# HEATER.net
KiCad netlist of a schematic drawn in Altium Designer
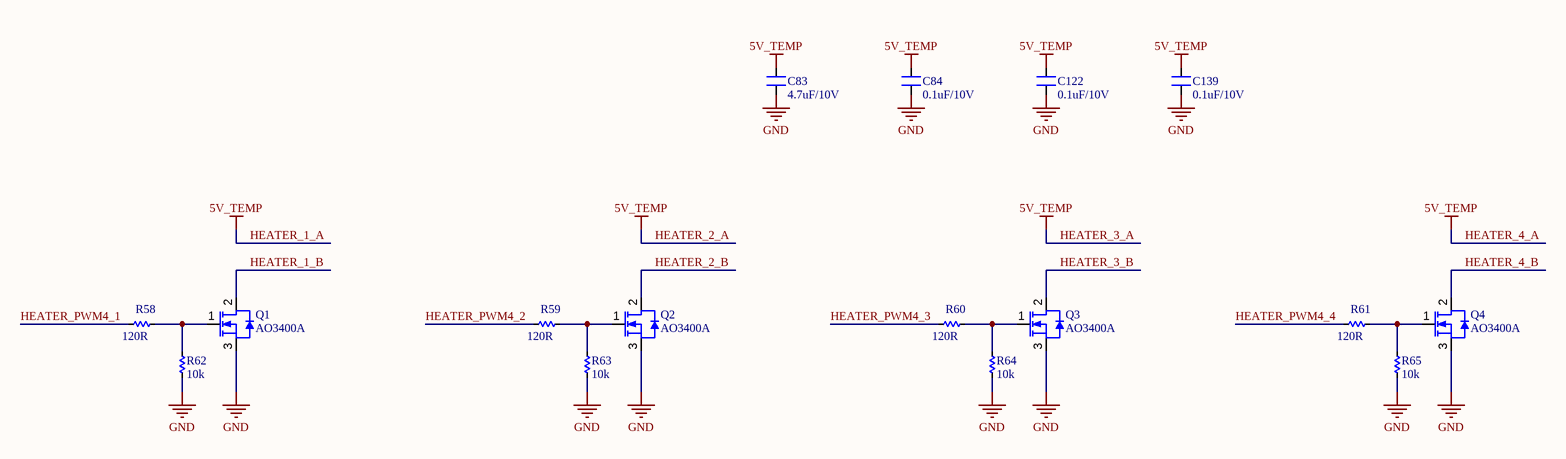
[diagram p0: HEATER.SchDoc]

(export (version "E")
  (design (tool "Eeschema 10.0.6"))
  (components
    (comp (ref "C83")
      (value "4.7uF/10V")
      (footprint "CAP_C_1608X80")
      (libsource (lib "EXP_HW_V3") (part "Capacitors"))
    )
    (comp (ref "C84")
      (value "0.1uF/10V")
      (footprint "CAP_C_1608X80")
      (libsource (lib "EXP_HW_V3") (part "Capacitors"))
    )
    (comp (ref "C122")
      (value "0.1uF/10V")
      (footprint "CAP_C_1608X80")
      (libsource (lib "EXP_HW_V3") (part "Capacitors"))
    )
    (comp (ref "C139")
      (value "0.1uF/10V")
      (footprint "CAP_C_1608X80")
      (libsource (lib "EXP_HW_V3") (part "Capacitors"))
    )
    (comp (ref "Q1")
      (value "AO3400A")
      (footprint "SOT23-13_2")
      (description "MOSFET N-CH 30V 5.7A SOT23-3L")
      (libsource (lib "EXP_HW_V3") (part "AO3400A"))
    )
    (comp (ref "Q2")
      (value "AO3400A")
      (footprint "SOT23-13_2")
      (description "MOSFET N-CH 30V 5.7A SOT23-3L")
      (libsource (lib "EXP_HW_V3") (part "AO3400A"))
    )
    (comp (ref "Q3")
      (value "AO3400A")
      (footprint "SOT23-13_2")
      (description "MOSFET N-CH 30V 5.7A SOT23-3L")
      (libsource (lib "EXP_HW_V3") (part "AO3400A"))
    )
    (comp (ref "Q4")
      (value "AO3400A")
      (footprint "SOT23-13_2")
      (description "MOSFET N-CH 30V 5.7A SOT23-3L")
      (libsource (lib "EXP_HW_V3") (part "AO3400A"))
    )
    (comp (ref "R58")
      (value "120R")
      (footprint "RES_C_1608X60")
      (description "SMD")
      (fields
        (field (name "MANUFACTURER") "Generic Components")
        (field (name "PUBLISHER") "Altium Hobart Technology Centre")
      )
      (libsource (lib "EXP_HW_V3") (part "Res SMD"))
    )
    (comp (ref "R59")
      (value "120R")
      (footprint "RES_C_1608X60")
      (description "SMD")
      (fields
        (field (name "MANUFACTURER") "Generic Components")
        (field (name "PUBLISHER") "Altium Hobart Technology Centre")
      )
      (libsource (lib "EXP_HW_V3") (part "Res SMD"))
    )
    (comp (ref "R60")
      (value "120R")
      (footprint "RES_C_1608X60")
      (description "SMD")
      (fields
        (field (name "MANUFACTURER") "Generic Components")
        (field (name "PUBLISHER") "Altium Hobart Technology Centre")
      )
      (libsource (lib "EXP_HW_V3") (part "Res SMD"))
    )
    (comp (ref "R61")
      (value "120R")
      (footprint "RES_C_1608X60")
      (description "SMD")
      (fields
        (field (name "MANUFACTURER") "Generic Components")
        (field (name "PUBLISHER") "Altium Hobart Technology Centre")
      )
      (libsource (lib "EXP_HW_V3") (part "Res SMD"))
    )
    (comp (ref "R62")
      (value "10k")
      (footprint "RES_C_1608X60")
      (description "SMD")
      (fields
        (field (name "MANUFACTURER") "Generic Components")
        (field (name "PUBLISHER") "Altium Hobart Technology Centre")
      )
      (libsource (lib "EXP_HW_V3") (part "Res SMD"))
    )
    (comp (ref "R63")
      (value "10k")
      (footprint "RES_C_1608X60")
      (description "SMD")
      (fields
        (field (name "MANUFACTURER") "Generic Components")
        (field (name "PUBLISHER") "Altium Hobart Technology Centre")
      )
      (libsource (lib "EXP_HW_V3") (part "Res SMD"))
    )
    (comp (ref "R64")
      (value "10k")
      (footprint "RES_C_1608X60")
      (description "SMD")
      (fields
        (field (name "MANUFACTURER") "Generic Components")
        (field (name "PUBLISHER") "Altium Hobart Technology Centre")
      )
      (libsource (lib "EXP_HW_V3") (part "Res SMD"))
    )
    (comp (ref "R65")
      (value "10k")
      (footprint "RES_C_1608X60")
      (description "SMD")
      (fields
        (field (name "MANUFACTURER") "Generic Components")
        (field (name "PUBLISHER") "Altium Hobart Technology Centre")
      )
      (libsource (lib "EXP_HW_V3") (part "Res SMD"))
    )
  )
  (nets
    (net (code "1") (name "/HEATER_1_B") (class "Default")
      (node (ref "Q1") (pin "2") (pinfunction "D_2") (pintype "passive"))
    )
    (net (code "2") (name "/HEATER_2_B") (class "Default")
      (node (ref "Q2") (pin "2") (pinfunction "D_2") (pintype "passive"))
    )
    (net (code "3") (name "/HEATER_3_B") (class "Default")
      (node (ref "Q3") (pin "2") (pinfunction "D_2") (pintype "passive"))
    )
    (net (code "4") (name "/HEATER_4_B") (class "Default")
      (node (ref "Q4") (pin "2") (pinfunction "D_2") (pintype "passive"))
    )
    (net (code "5") (name "/HEATER_PWM4_1") (class "Default")
      (node (ref "R58") (pin "1") (pinfunction "1_1") (pintype "passive"))
    )
    (net (code "6") (name "/HEATER_PWM4_2") (class "Default")
      (node (ref "R59") (pin "1") (pinfunction "1_1") (pintype "passive"))
    )
    (net (code "7") (name "/HEATER_PWM4_3") (class "Default")
      (node (ref "R60") (pin "1") (pinfunction "1_1") (pintype "passive"))
    )
    (net (code "8") (name "/HEATER_PWM4_4") (class "Default")
      (node (ref "R61") (pin "1") (pinfunction "1_1") (pintype "passive"))
    )
    (net (code "9") (name "5V_TEMP") (class "Default")
      (node (ref "C122") (pin "2") (pinfunction "2_2") (pintype "passive"))
      (node (ref "C139") (pin "2") (pinfunction "2_2") (pintype "passive"))
      (node (ref "C83") (pin "2") (pinfunction "2_2") (pintype "passive"))
      (node (ref "C84") (pin "2") (pinfunction "2_2") (pintype "passive"))
    )
    (net (code "10") (name "GND") (class "Default")
      (node (ref "C122") (pin "1") (pinfunction "1_1") (pintype "passive"))
      (node (ref "C139") (pin "1") (pinfunction "1_1") (pintype "passive"))
      (node (ref "C83") (pin "1") (pinfunction "1_1") (pintype "passive"))
      (node (ref "C84") (pin "1") (pinfunction "1_1") (pintype "passive"))
      (node (ref "Q1") (pin "3") (pinfunction "S_3") (pintype "passive"))
      (node (ref "Q2") (pin "3") (pinfunction "S_3") (pintype "passive"))
      (node (ref "Q3") (pin "3") (pinfunction "S_3") (pintype "passive"))
      (node (ref "Q4") (pin "3") (pinfunction "S_3") (pintype "passive"))
      (node (ref "R62") (pin "1") (pinfunction "1_1") (pintype "passive"))
      (node (ref "R63") (pin "1") (pinfunction "1_1") (pintype "passive"))
      (node (ref "R64") (pin "1") (pinfunction "1_1") (pintype "passive"))
      (node (ref "R65") (pin "1") (pinfunction "1_1") (pintype "passive"))
    )
    (net (code "11") (name "Net-(Q1-G)") (class "Default")
      (node (ref "Q1") (pin "1") (pinfunction "G_1") (pintype "passive"))
      (node (ref "R58") (pin "2") (pinfunction "2_2") (pintype "passive"))
      (node (ref "R62") (pin "2") (pinfunction "2_2") (pintype "passive"))
    )
    (net (code "12") (name "Net-(Q2-G)") (class "Default")
      (node (ref "Q2") (pin "1") (pinfunction "G_1") (pintype "passive"))
      (node (ref "R59") (pin "2") (pinfunction "2_2") (pintype "passive"))
      (node (ref "R63") (pin "2") (pinfunction "2_2") (pintype "passive"))
    )
    (net (code "13") (name "Net-(Q3-G)") (class "Default")
      (node (ref "Q3") (pin "1") (pinfunction "G_1") (pintype "passive"))
      (node (ref "R60") (pin "2") (pinfunction "2_2") (pintype "passive"))
      (node (ref "R64") (pin "2") (pinfunction "2_2") (pintype "passive"))
    )
    (net (code "14") (name "Net-(Q4-G)") (class "Default")
      (node (ref "Q4") (pin "1") (pinfunction "G_1") (pintype "passive"))
      (node (ref "R61") (pin "2") (pinfunction "2_2") (pintype "passive"))
      (node (ref "R65") (pin "2") (pinfunction "2_2") (pintype "passive"))
    )
  )
)
